# microsd_schematic.net
KiCad netlist of a schematic drawn in EAGLE
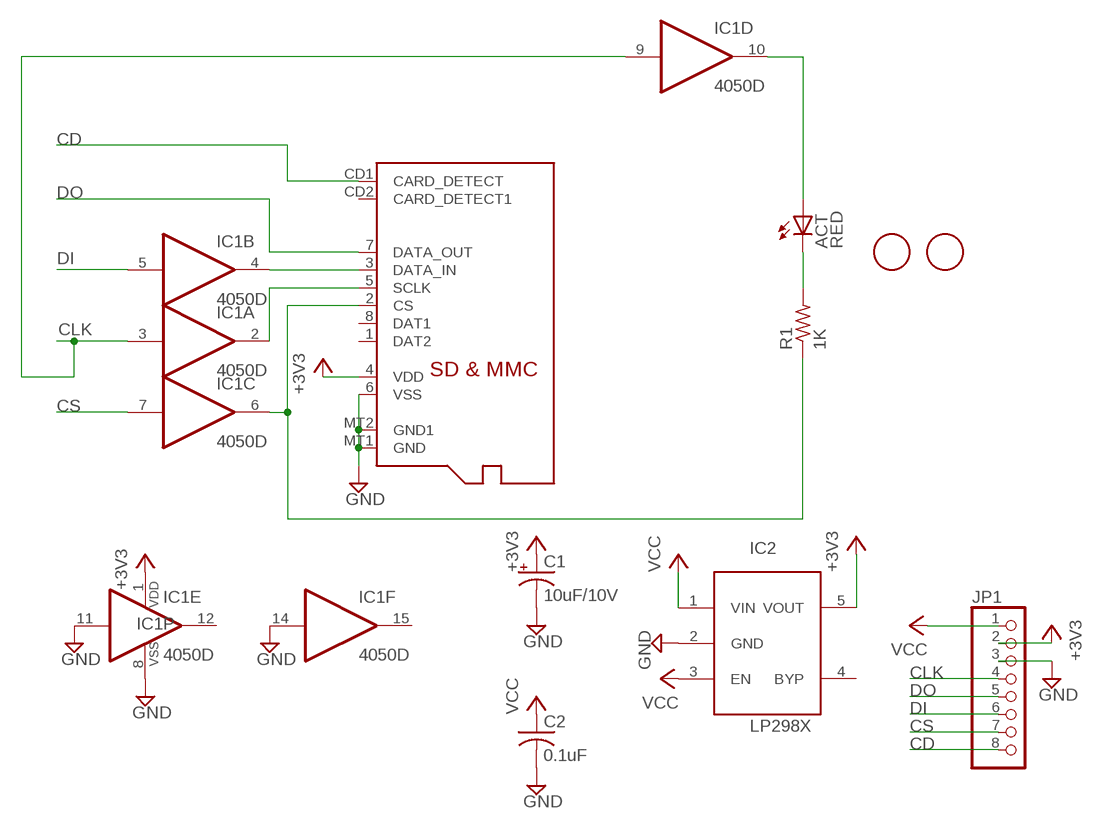
[diagram p0: schematic, sheet 1]

(export (version "E")
  (design (tool "Eeschema 10.0.6"))
  (components
    (comp (ref "ACT")
      (value "RED")
      (footprint "eagle-import:CHIP-LED0805")
      (libsource (lib "eagle-import") (part "LEDCHIP-LED0805"))
    )
    (comp (ref "C1")
      (value "10uF/10V")
      (footprint "eagle-import:A_3216-18R")
      (libsource (lib "eagle-import") (part "CPOL-USA/3216-18R"))
    )
    (comp (ref "C2")
      (value "0.1uF")
      (footprint "eagle-import:C0805K")
      (libsource (lib "eagle-import") (part "C-USC0805K"))
    )
    (comp (ref "IC1")
      (value "4050D")
      (footprint "eagle-import:SO16")
      (libsource (lib "eagle-import") (part "4050D"))
    )
    (comp (ref "IC2")
      (value "LP298XS")
      (footprint "eagle-import:SOT23-5L")
      (libsource (lib "eagle-import") (part "LP298XS"))
    )
    (comp (ref "JP1")
      (value "PINHD-1X8BIG")
      (footprint "eagle-import:1X08-BIG")
      (libsource (lib "eagle-import") (part "PINHD-1X8BIG"))
    )
    (comp (ref "R1")
      (value "1K")
      (footprint "eagle-import:R0805")
      (libsource (lib "eagle-import") (part "R-US_R0805"))
    )
    (comp (ref "U$1")
      (value "FIDUCIAL")
      (footprint "eagle-import:FIDUCIAL_1MM")
      (libsource (lib "eagle-import") (part "FIDUCIAL"))
    )
    (comp (ref "U$2")
      (value "FIDUCIAL")
      (footprint "eagle-import:FIDUCIAL_1MM")
      (libsource (lib "eagle-import") (part "FIDUCIAL"))
    )
    (comp (ref "X1")
      (value "MICROSD")
      (footprint "eagle-import:MICROSD")
      (libsource (lib "eagle-import") (part "MICROSD"))
    )
  )
  (nets
    (net (code "1") (name "+3V3") (class "Default")
      (node (ref "C1") (pin "+") (pinfunction "+_+") (pintype "passive"))
      (node (ref "IC1") (pin "1") (pinfunction "VDD_1") (pintype "power_in"))
      (node (ref "IC2") (pin "5") (pinfunction "VOUT_5") (pintype "bidirectional"))
      (node (ref "JP1") (pin "2") (pinfunction "2_2") (pintype "passive"))
      (node (ref "X1") (pin "4") (pinfunction "VDD_4") (pintype "power_in"))
    )
    (net (code "2") (name "/CD") (class "Default")
      (node (ref "JP1") (pin "8") (pinfunction "8_8") (pintype "passive"))
      (node (ref "X1") (pin "CD1") (pinfunction "CARD_DETECT_CD1") (pintype "passive"))
    )
    (net (code "3") (name "/CLK") (class "Default")
      (node (ref "IC1") (pin "3") (pinfunction "I_3") (pintype "input"))
      (node (ref "IC1") (pin "9") (pinfunction "I_9") (pintype "input"))
      (node (ref "JP1") (pin "4") (pinfunction "4_4") (pintype "passive"))
    )
    (net (code "4") (name "/CS") (class "Default")
      (node (ref "IC1") (pin "7") (pinfunction "I_7") (pintype "input"))
      (node (ref "JP1") (pin "7") (pinfunction "7_7") (pintype "passive"))
    )
    (net (code "5") (name "/DI") (class "Default")
      (node (ref "IC1") (pin "5") (pinfunction "I_5") (pintype "input"))
      (node (ref "JP1") (pin "6") (pinfunction "6_6") (pintype "passive"))
    )
    (net (code "6") (name "/DO") (class "Default")
      (node (ref "JP1") (pin "5") (pinfunction "5_5") (pintype "passive"))
      (node (ref "X1") (pin "7") (pinfunction "DATA_OUT_7") (pintype "output"))
    )
    (net (code "7") (name "GND") (class "Default")
      (node (ref "C1") (pin "-") (pinfunction "-_-") (pintype "passive"))
      (node (ref "C2") (pin "2") (pinfunction "2_2") (pintype "passive"))
      (node (ref "IC1") (pin "11") (pinfunction "I_11") (pintype "input"))
      (node (ref "IC1") (pin "14") (pinfunction "I_14") (pintype "input"))
      (node (ref "IC1") (pin "8") (pinfunction "VSS_8") (pintype "power_in"))
      (node (ref "IC2") (pin "2") (pinfunction "GND_2") (pintype "bidirectional"))
      (node (ref "JP1") (pin "3") (pinfunction "3_3") (pintype "passive"))
      (node (ref "X1") (pin "6") (pinfunction "VSS_6") (pintype "power_in"))
      (node (ref "X1") (pin "MT1") (pinfunction "GND_MT1") (pintype "power_in"))
      (node (ref "X1") (pin "MT2") (pinfunction "GND1_MT2") (pintype "power_in"))
    )
    (net (code "8") (name "Net-(ACT-PadC)") (class "Default")
      (node (ref "ACT") (pin "C") (pinfunction "C_C") (pintype "passive"))
      (node (ref "R1") (pin "2") (pinfunction "2_2") (pintype "passive"))
    )
    (net (code "9") (name "Net-(IC1A-O)") (class "Default")
      (node (ref "IC1") (pin "2") (pinfunction "O_2") (pintype "output"))
      (node (ref "X1") (pin "5") (pinfunction "SCLK_5") (pintype "input"))
    )
    (net (code "10") (name "Net-(IC1B-O)") (class "Default")
      (node (ref "IC1") (pin "4") (pinfunction "O_4") (pintype "output"))
      (node (ref "X1") (pin "3") (pinfunction "DATA_IN_3") (pintype "input"))
    )
    (net (code "11") (name "Net-(IC1C-O)") (class "Default")
      (node (ref "IC1") (pin "6") (pinfunction "O_6") (pintype "output"))
      (node (ref "R1") (pin "1") (pinfunction "1_1") (pintype "passive"))
      (node (ref "X1") (pin "2") (pinfunction "CS_2") (pintype "input"))
    )
    (net (code "12") (name "Net-(IC1D-O)") (class "Default")
      (node (ref "ACT") (pin "A") (pinfunction "A_A") (pintype "passive"))
      (node (ref "IC1") (pin "10") (pinfunction "O_10") (pintype "output"))
    )
    (net (code "13") (name "VCC") (class "Default")
      (node (ref "C2") (pin "1") (pinfunction "1_1") (pintype "passive"))
      (node (ref "IC2") (pin "1") (pinfunction "VIN_1") (pintype "bidirectional"))
      (node (ref "IC2") (pin "3") (pinfunction "EN_3") (pintype "bidirectional"))
      (node (ref "JP1") (pin "1") (pinfunction "1_1") (pintype "passive"))
    )
    (net (code "14") (name "unconnected-(IC1E-O-Pad12)") (class "Default")
      (node (ref "IC1") (pin "12") (pinfunction "O_12") (pintype "output"))
    )
    (net (code "15") (name "unconnected-(IC1F-O-Pad15)") (class "Default")
      (node (ref "IC1") (pin "15") (pinfunction "O_15") (pintype "output"))
    )
    (net (code "16") (name "unconnected-(IC2-BYP-Pad4)") (class "Default")
      (node (ref "IC2") (pin "4") (pinfunction "BYP_4") (pintype "bidirectional"))
    )
    (net (code "17") (name "unconnected-(X1-CARD_DETECT1-PadCD2)") (class "Default")
      (node (ref "X1") (pin "CD2") (pinfunction "CARD_DETECT1_CD2") (pintype "passive"))
    )
    (net (code "18") (name "unconnected-(X1-DAT1-Pad8)") (class "Default")
      (node (ref "X1") (pin "8") (pinfunction "DAT1_8") (pintype "bidirectional"))
    )
    (net (code "19") (name "unconnected-(X1-DAT2-Pad1)") (class "Default")
      (node (ref "X1") (pin "1") (pinfunction "DAT2_1") (pintype "bidirectional"))
    )
  )
)
